# TD_0002-100_1.net
KiCad netlist of a schematic drawn in Altium Designer
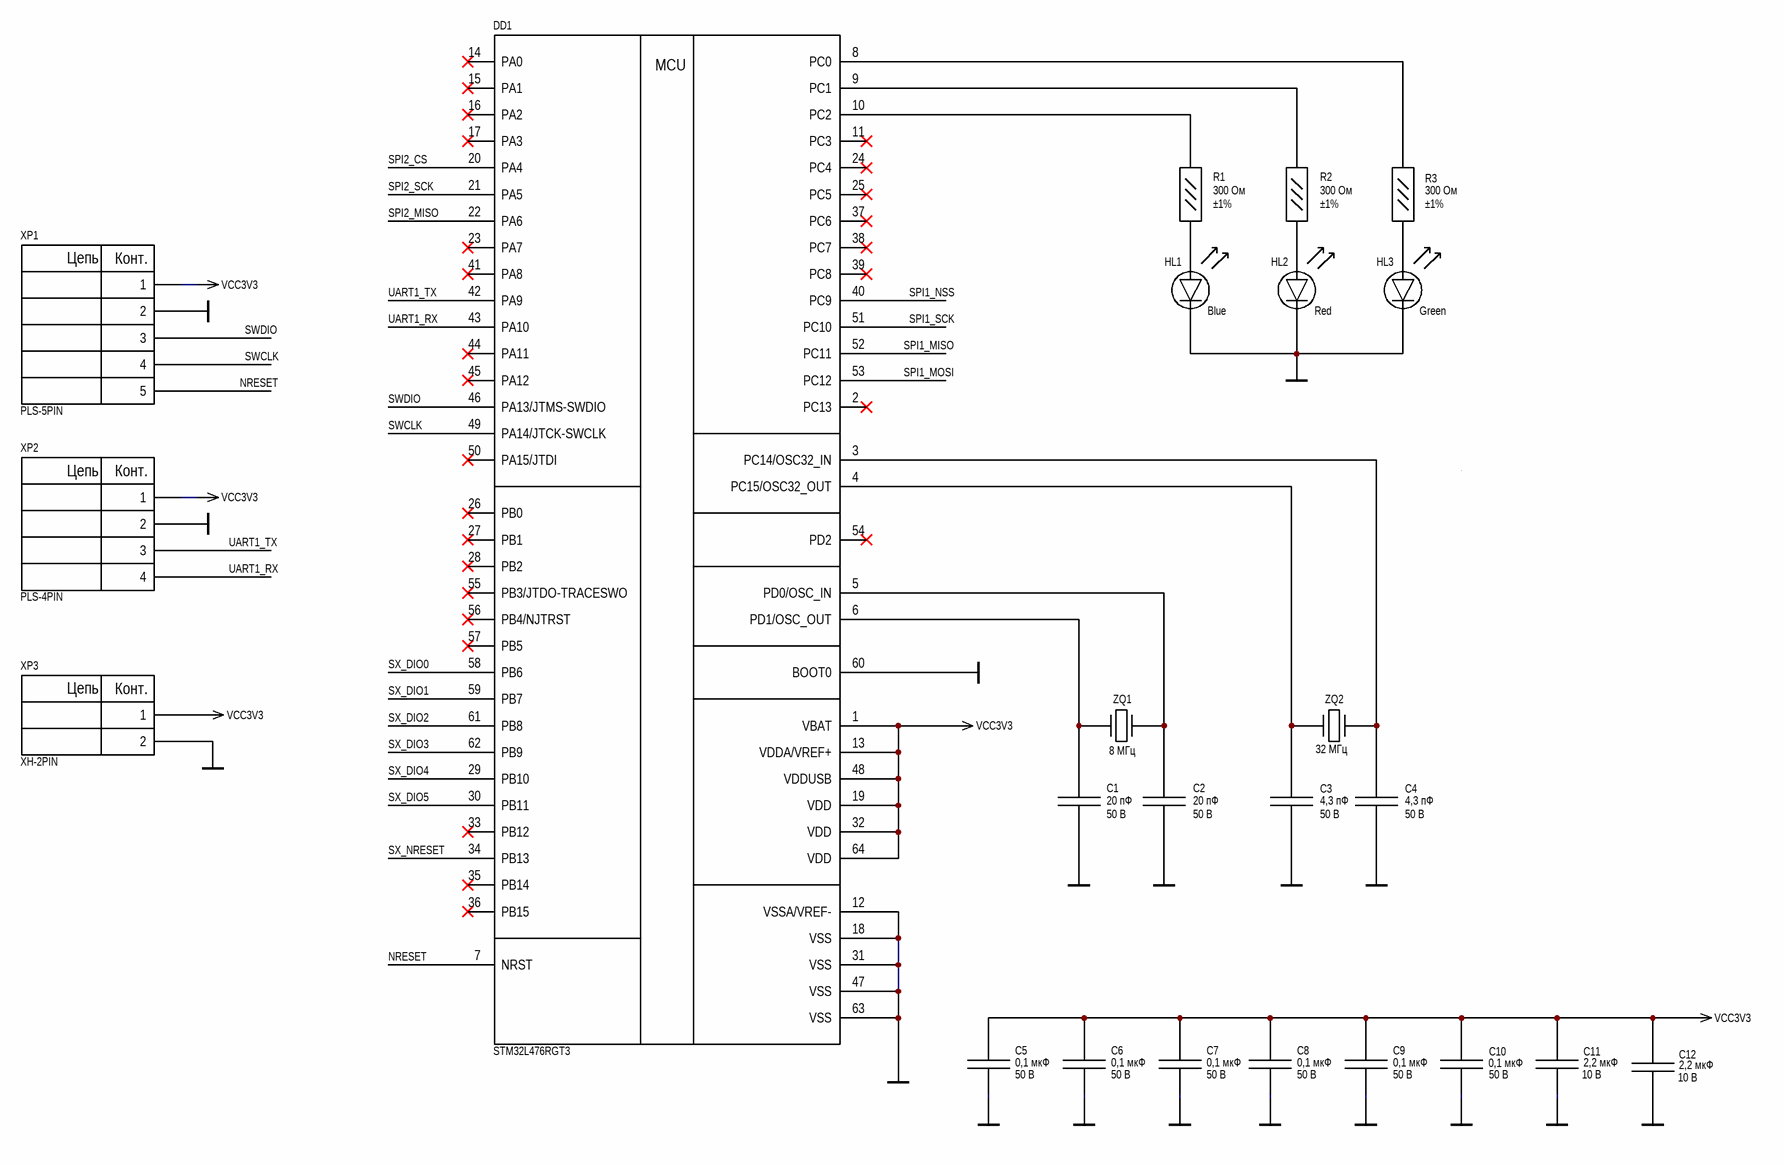
[diagram p0: TD.0002-100_1.SchDoc]

(export (version "E")
  (design (tool "Eeschema 10.0.6"))
  (components
    (comp (ref "C1")
      (value "20 пФ")
      (footprint "C_0402")
      (description "Chip Multilayer Ceramic Capacitor")
      (fields
        (field (name "PART NUMBER") "GCM1555C1H200JA16")
        (field (name "MANUFACTURER") "Murata")
        (field (name "VOLTAGE") "50 В")
      )
      (libsource (lib "Database_Libs") (part "Capacitor"))
    )
    (comp (ref "C2")
      (value "20 пФ")
      (footprint "C_0402")
      (description "Chip Multilayer Ceramic Capacitor")
      (fields
        (field (name "PART NUMBER") "GCM1555C1H200JA16")
        (field (name "MANUFACTURER") "Murata")
        (field (name "VOLTAGE") "50 В")
      )
      (libsource (lib "Database_Libs") (part "Capacitor"))
    )
    (comp (ref "C3")
      (value "4,3 пФ")
      (footprint "C_0402")
      (description "Chip Multilayer Ceramic Capacitor")
      (fields
        (field (name "PART NUMBER") "GCM1555C1H4R3BA16")
        (field (name "MANUFACTURER") "Murata")
        (field (name "VOLTAGE") "50 В")
      )
      (libsource (lib "Database_Libs") (part "Capacitor"))
    )
    (comp (ref "C4")
      (value "4,3 пФ")
      (footprint "C_0402")
      (description "Chip Multilayer Ceramic Capacitor")
      (fields
        (field (name "PART NUMBER") "GCM1555C1H4R3BA16")
        (field (name "MANUFACTURER") "Murata")
        (field (name "VOLTAGE") "50 В")
      )
      (libsource (lib "Database_Libs") (part "Capacitor"))
    )
    (comp (ref "C5")
      (value "0,1 мкФ")
      (footprint "C_0402")
      (description "Chip Multilayer Ceramic Capacitor")
      (fields
        (field (name "PART NUMBER") "GRM155R71H104KE14")
        (field (name "MANUFACTURER") "Murata")
        (field (name "VOLTAGE") "50 В")
      )
      (libsource (lib "Database_Libs") (part "Capacitor"))
    )
    (comp (ref "C6")
      (value "0,1 мкФ")
      (footprint "C_0402")
      (description "Chip Multilayer Ceramic Capacitor")
      (fields
        (field (name "PART NUMBER") "GRM155R71H104KE14")
        (field (name "MANUFACTURER") "Murata")
        (field (name "VOLTAGE") "50 В")
      )
      (libsource (lib "Database_Libs") (part "Capacitor"))
    )
    (comp (ref "C7")
      (value "0,1 мкФ")
      (footprint "C_0402")
      (description "Chip Multilayer Ceramic Capacitor")
      (fields
        (field (name "PART NUMBER") "GRM155R71H104KE14")
        (field (name "MANUFACTURER") "Murata")
        (field (name "VOLTAGE") "50 В")
      )
      (libsource (lib "Database_Libs") (part "Capacitor"))
    )
    (comp (ref "C8")
      (value "0,1 мкФ")
      (footprint "C_0402")
      (description "Chip Multilayer Ceramic Capacitor")
      (fields
        (field (name "PART NUMBER") "GRM155R71H104KE14")
        (field (name "MANUFACTURER") "Murata")
        (field (name "VOLTAGE") "50 В")
      )
      (libsource (lib "Database_Libs") (part "Capacitor"))
    )
    (comp (ref "C9")
      (value "0,1 мкФ")
      (footprint "C_0402")
      (description "Chip Multilayer Ceramic Capacitor")
      (fields
        (field (name "PART NUMBER") "GRM155R71H104KE14")
        (field (name "MANUFACTURER") "Murata")
        (field (name "VOLTAGE") "50 В")
      )
      (libsource (lib "Database_Libs") (part "Capacitor"))
    )
    (comp (ref "C10")
      (value "0,1 мкФ")
      (footprint "C_0402")
      (description "Chip Multilayer Ceramic Capacitor")
      (fields
        (field (name "PART NUMBER") "GRM155R71H104KE14")
        (field (name "MANUFACTURER") "Murata")
        (field (name "VOLTAGE") "50 В")
      )
      (libsource (lib "Database_Libs") (part "Capacitor"))
    )
    (comp (ref "C11")
      (value "2,2 мкФ")
      (footprint "C_0402")
      (description "Chip Multilayer Ceramic Capacitor")
      (fields
        (field (name "PART NUMBER") "GRM155C81A225ME44")
        (field (name "MANUFACTURER") "Murata")
        (field (name "VOLTAGE") "10 В")
      )
      (libsource (lib "Database_Libs") (part "Capacitor"))
    )
    (comp (ref "C12")
      (value "2,2 мкФ")
      (footprint "C_0402")
      (description "Chip Multilayer Ceramic Capacitor")
      (fields
        (field (name "PART NUMBER") "GRM155C81A225ME44")
        (field (name "MANUFACTURER") "Murata")
        (field (name "VOLTAGE") "10 В")
      )
      (libsource (lib "Database_Libs") (part "Capacitor"))
    )
    (comp (ref "DD1")
      (value "STM32L476RGT3")
      (footprint "FirstLib:LQFP_64")
      (fields (field (name "MANUFACTURER") "STMicroelectronics"))
      (libsource (lib "FirstLib") (part "STM32L476RGT3"))
    )
    (comp (ref "HL1")
      (value "TO-2013BC-BF")
      (footprint "LED_0805_BLUE")
      (description "Светодиод синий")
      (fields (field (name "COLOR") "Blue") (field (name "MANUFACTURER") "OASISTEK"))
      (libsource (lib "Database_Libs") (part "LED"))
    )
    (comp (ref "HL2")
      (value "TO-2013BC-MRE")
      (footprint "LED_0805_RED")
      (description "Светодиод красный")
      (fields (field (name "COLOR") "Red") (field (name "MANUFACTURER") "OASISTEK"))
      (libsource (lib "Database_Libs") (part "LED"))
    )
    (comp (ref "HL3")
      (value "TO-2013BC-PG")
      (footprint "LED_0805_GREEN")
      (description "Светодиод зеленый")
      (fields (field (name "COLOR") "Green") (field (name "MANUFACTURER") "OASISTEK"))
      (libsource (lib "Database_Libs") (part "LED"))
    )
    (comp (ref "R1")
      (value "300 Ом")
      (footprint "R_0402")
      (description "General Purpose")
      (fields
        (field (name "ACCURACY") "±1%")
        (field (name "PART NUMBER") "RC0100FR-07300RP")
        (field (name "VOLTAGE") "15 В")
      )
      (libsource (lib "Database_Libs") (part "Resistor_0.05W"))
    )
    (comp (ref "R2")
      (value "300 Ом")
      (footprint "R_0402")
      (description "General Purpose")
      (fields
        (field (name "ACCURACY") "±1%")
        (field (name "PART NUMBER") "RC0100FR-07300RP")
        (field (name "VOLTAGE") "15 В")
      )
      (libsource (lib "Database_Libs") (part "Resistor_0.05W"))
    )
    (comp (ref "R3")
      (value "300 Ом")
      (footprint "R_0402")
      (description "General Purpose")
      (fields
        (field (name "ACCURACY") "±1%")
        (field (name "PART NUMBER") "RC0100FR-07300RP")
        (field (name "VOLTAGE") "15 В")
      )
      (libsource (lib "Database_Libs") (part "Resistor_0.05W"))
    )
    (comp (ref "XP1")
      (value "PLS-5PIN")
      (footprint "FirstLib:PLS-5PIN")
      (libsource (lib "FirstLib") (part "PLS-5PIN"))
    )
    (comp (ref "XP2")
      (value "PLS-4PIN")
      (footprint "FirstLib:PLS-4PIN")
      (libsource (lib "FirstLib") (part "PLS-4PIN"))
    )
    (comp (ref "XP3")
      (value "XH-2PIN")
      (footprint "FirstLib:XH-2PIN")
      (fields (field (name "VOLTAGE") "250 V"))
      (libsource (lib "FirstLib") (part "XH-2PIN"))
    )
    (comp (ref "ZQ1")
      (value "8 МГц")
      (footprint "FirstLib:CM9V-T1A")
      (fields (field (name "Comment") "Quartz"))
      (libsource (lib "FirstLib") (part "Quartz"))
    )
    (comp (ref "ZQ2")
      (value "32 МГц")
      (footprint "FirstLib:CM9V-T1A")
      (fields (field (name "Comment") "Quartz"))
      (libsource (lib "FirstLib") (part "Quartz"))
    )
  )
  (nets
    (net (code "1") (name "/NRESET") (class "Default")
      (node (ref "DD1") (pin "7") (pinfunction "NRST_7") (pintype "passive"))
      (node (ref "XP1") (pin "5") (pinfunction "5_5") (pintype "passive"))
    )
    (net (code "2") (name "/SPI1_MISO") (class "Default")
      (node (ref "DD1") (pin "52") (pinfunction "PC11_52") (pintype "passive"))
    )
    (net (code "3") (name "/SPI1_MOSI") (class "Default")
      (node (ref "DD1") (pin "53") (pinfunction "PC12_53") (pintype "passive"))
    )
    (net (code "4") (name "/SPI1_NSS") (class "Default")
      (node (ref "DD1") (pin "40") (pinfunction "PC9_40") (pintype "passive"))
    )
    (net (code "5") (name "/SPI1_SCK") (class "Default")
      (node (ref "DD1") (pin "51") (pinfunction "PC10_51") (pintype "passive"))
    )
    (net (code "6") (name "/SPI2_CS") (class "Default")
      (node (ref "DD1") (pin "20") (pinfunction "PA4_20") (pintype "passive"))
    )
    (net (code "7") (name "/SPI2_MISO") (class "Default")
      (node (ref "DD1") (pin "22") (pinfunction "PA6_22") (pintype "passive"))
    )
    (net (code "8") (name "/SPI2_SCK") (class "Default")
      (node (ref "DD1") (pin "21") (pinfunction "PA5_21") (pintype "passive"))
    )
    (net (code "9") (name "/SWCLK") (class "Default")
      (node (ref "DD1") (pin "49") (pinfunction "PA14/JTCK-SWCLK_49") (pintype "passive"))
      (node (ref "XP1") (pin "4") (pinfunction "4_4") (pintype "passive"))
    )
    (net (code "10") (name "/SWDIO") (class "Default")
      (node (ref "DD1") (pin "46") (pinfunction "PA13/JTMS-SWDIO_46") (pintype "passive"))
      (node (ref "XP1") (pin "3") (pinfunction "3_3") (pintype "passive"))
    )
    (net (code "11") (name "/SX_DIO0") (class "Default")
      (node (ref "DD1") (pin "58") (pinfunction "PB6_58") (pintype "passive"))
    )
    (net (code "12") (name "/SX_DIO1") (class "Default")
      (node (ref "DD1") (pin "59") (pinfunction "PB7_59") (pintype "passive"))
    )
    (net (code "13") (name "/SX_DIO2") (class "Default")
      (node (ref "DD1") (pin "61") (pinfunction "PB8_61") (pintype "passive"))
    )
    (net (code "14") (name "/SX_DIO3") (class "Default")
      (node (ref "DD1") (pin "62") (pinfunction "PB9_62") (pintype "passive"))
    )
    (net (code "15") (name "/SX_DIO4") (class "Default")
      (node (ref "DD1") (pin "29") (pinfunction "PB10_29") (pintype "passive"))
    )
    (net (code "16") (name "/SX_DIO5") (class "Default")
      (node (ref "DD1") (pin "30") (pinfunction "PB11_30") (pintype "passive"))
    )
    (net (code "17") (name "/SX_NRESET") (class "Default")
      (node (ref "DD1") (pin "34") (pinfunction "PB13_34") (pintype "passive"))
    )
    (net (code "18") (name "/UART1_RX") (class "Default")
      (node (ref "DD1") (pin "43") (pinfunction "PA10_43") (pintype "passive"))
      (node (ref "XP2") (pin "4") (pinfunction "4_4") (pintype "passive"))
    )
    (net (code "19") (name "/UART1_TX") (class "Default")
      (node (ref "DD1") (pin "42") (pinfunction "PA9_42") (pintype "passive"))
      (node (ref "XP2") (pin "3") (pinfunction "3_3") (pintype "passive"))
    )
    (net (code "20") (name "GND") (class "Default")
      (node (ref "C1") (pin "2") (pinfunction "2_2") (pintype "passive"))
      (node (ref "C10") (pin "2") (pinfunction "2_2") (pintype "passive"))
      (node (ref "C11") (pin "2") (pinfunction "2_2") (pintype "passive"))
      (node (ref "C12") (pin "2") (pinfunction "2_2") (pintype "passive"))
      (node (ref "C2") (pin "2") (pinfunction "2_2") (pintype "passive"))
      (node (ref "C3") (pin "2") (pinfunction "2_2") (pintype "passive"))
      (node (ref "C4") (pin "2") (pinfunction "2_2") (pintype "passive"))
      (node (ref "C5") (pin "2") (pinfunction "2_2") (pintype "passive"))
      (node (ref "C6") (pin "2") (pinfunction "2_2") (pintype "passive"))
      (node (ref "C7") (pin "2") (pinfunction "2_2") (pintype "passive"))
      (node (ref "C8") (pin "2") (pinfunction "2_2") (pintype "passive"))
      (node (ref "C9") (pin "2") (pinfunction "2_2") (pintype "passive"))
      (node (ref "DD1") (pin "12") (pinfunction "VSSA/VREF-_12") (pintype "passive"))
      (node (ref "DD1") (pin "18") (pinfunction "VSS_18") (pintype "passive"))
      (node (ref "DD1") (pin "31") (pinfunction "VSS_31") (pintype "passive"))
      (node (ref "DD1") (pin "47") (pinfunction "VSS_47") (pintype "passive"))
      (node (ref "DD1") (pin "60") (pinfunction "BOOT0_60") (pintype "passive"))
      (node (ref "DD1") (pin "63") (pinfunction "VSS_63") (pintype "passive"))
      (node (ref "HL1") (pin "2") (pinfunction "2_2") (pintype "passive"))
      (node (ref "HL2") (pin "2") (pinfunction "2_2") (pintype "passive"))
      (node (ref "HL3") (pin "2") (pinfunction "2_2") (pintype "passive"))
      (node (ref "XP1") (pin "2") (pinfunction "2_2") (pintype "passive"))
      (node (ref "XP2") (pin "2") (pinfunction "2_2") (pintype "passive"))
      (node (ref "XP3") (pin "2") (pinfunction "2_2") (pintype "passive"))
    )
    (net (code "21") (name "Net-(DD1-PC0)") (class "Default")
      (node (ref "DD1") (pin "8") (pinfunction "PC0_8") (pintype "passive"))
      (node (ref "R3") (pin "2") (pinfunction "2_2") (pintype "passive"))
    )
    (net (code "22") (name "Net-(DD1-PC1)") (class "Default")
      (node (ref "DD1") (pin "9") (pinfunction "PC1_9") (pintype "passive"))
      (node (ref "R2") (pin "2") (pinfunction "2_2") (pintype "passive"))
    )
    (net (code "23") (name "Net-(DD1-PC2)") (class "Default")
      (node (ref "DD1") (pin "10") (pinfunction "PC2_10") (pintype "passive"))
      (node (ref "R1") (pin "2") (pinfunction "2_2") (pintype "passive"))
    )
    (net (code "24") (name "Net-(DD1-PC14{slash}OSC32_IN)") (class "Default")
      (node (ref "C4") (pin "1") (pinfunction "1_1") (pintype "passive"))
      (node (ref "DD1") (pin "3") (pinfunction "PC14/OSC32_IN_3") (pintype "passive"))
      (node (ref "ZQ2") (pin "2") (pinfunction "XO_2") (pintype "passive"))
    )
    (net (code "25") (name "Net-(DD1-PC15{slash}OSC32_OUT)") (class "Default")
      (node (ref "C3") (pin "1") (pinfunction "1_1") (pintype "passive"))
      (node (ref "DD1") (pin "4") (pinfunction "PC15/OSC32_OUT_4") (pintype "passive"))
      (node (ref "ZQ2") (pin "1") (pinfunction "XI_1") (pintype "passive"))
    )
    (net (code "26") (name "Net-(DD1-PD0{slash}OSC_IN)") (class "Default")
      (node (ref "C2") (pin "1") (pinfunction "1_1") (pintype "passive"))
      (node (ref "DD1") (pin "5") (pinfunction "PD0/OSC_IN_5") (pintype "passive"))
      (node (ref "ZQ1") (pin "1") (pinfunction "XI_1") (pintype "passive"))
    )
    (net (code "27") (name "Net-(DD1-PD1{slash}OSC_OUT)") (class "Default")
      (node (ref "C1") (pin "1") (pinfunction "1_1") (pintype "passive"))
      (node (ref "DD1") (pin "6") (pinfunction "PD1/OSC_OUT_6") (pintype "passive"))
      (node (ref "ZQ1") (pin "2") (pinfunction "XO_2") (pintype "passive"))
    )
    (net (code "28") (name "Net-(HL1-Pad1)") (class "Default")
      (node (ref "HL1") (pin "1") (pinfunction "1_1") (pintype "passive"))
      (node (ref "R1") (pin "1") (pinfunction "1_1") (pintype "passive"))
    )
    (net (code "29") (name "Net-(HL2-Pad1)") (class "Default")
      (node (ref "HL2") (pin "1") (pinfunction "1_1") (pintype "passive"))
      (node (ref "R2") (pin "1") (pinfunction "1_1") (pintype "passive"))
    )
    (net (code "30") (name "Net-(HL3-Pad1)") (class "Default")
      (node (ref "HL3") (pin "1") (pinfunction "1_1") (pintype "passive"))
      (node (ref "R3") (pin "1") (pinfunction "1_1") (pintype "passive"))
    )
    (net (code "31") (name "VCC3V3") (class "Default")
      (node (ref "C10") (pin "1") (pinfunction "1_1") (pintype "passive"))
      (node (ref "C11") (pin "1") (pinfunction "1_1") (pintype "passive"))
      (node (ref "C12") (pin "1") (pinfunction "1_1") (pintype "passive"))
      (node (ref "C5") (pin "1") (pinfunction "1_1") (pintype "passive"))
      (node (ref "C6") (pin "1") (pinfunction "1_1") (pintype "passive"))
      (node (ref "C7") (pin "1") (pinfunction "1_1") (pintype "passive"))
      (node (ref "C8") (pin "1") (pinfunction "1_1") (pintype "passive"))
      (node (ref "C9") (pin "1") (pinfunction "1_1") (pintype "passive"))
      (node (ref "DD1") (pin "1") (pinfunction "VBAT_1") (pintype "passive"))
      (node (ref "DD1") (pin "13") (pinfunction "VDDA/VREF+_13") (pintype "passive"))
      (node (ref "DD1") (pin "19") (pinfunction "VDD_19") (pintype "passive"))
      (node (ref "DD1") (pin "32") (pinfunction "VDD_32") (pintype "passive"))
      (node (ref "DD1") (pin "48") (pinfunction "VDDUSB_48") (pintype "passive"))
      (node (ref "DD1") (pin "64") (pinfunction "VDD_64") (pintype "passive"))
      (node (ref "XP1") (pin "1") (pinfunction "1_1") (pintype "passive"))
      (node (ref "XP2") (pin "1") (pinfunction "1_1") (pintype "passive"))
      (node (ref "XP3") (pin "1") (pinfunction "1_1") (pintype "passive"))
    )
    (net (code "32") (name "unconnected-(DD1-PA0-Pad14)") (class "Default")
      (node (ref "DD1") (pin "14") (pinfunction "PA0_14") (pintype "passive+no_connect"))
    )
    (net (code "33") (name "unconnected-(DD1-PA1-Pad15)") (class "Default")
      (node (ref "DD1") (pin "15") (pinfunction "PA1_15") (pintype "passive+no_connect"))
    )
    (net (code "34") (name "unconnected-(DD1-PA2-Pad16)") (class "Default")
      (node (ref "DD1") (pin "16") (pinfunction "PA2_16") (pintype "passive+no_connect"))
    )
    (net (code "35") (name "unconnected-(DD1-PA3-Pad17)") (class "Default")
      (node (ref "DD1") (pin "17") (pinfunction "PA3_17") (pintype "passive+no_connect"))
    )
    (net (code "36") (name "unconnected-(DD1-PA7-Pad23)") (class "Default")
      (node (ref "DD1") (pin "23") (pinfunction "PA7_23") (pintype "passive+no_connect"))
    )
    (net (code "37") (name "unconnected-(DD1-PA8-Pad41)") (class "Default")
      (node (ref "DD1") (pin "41") (pinfunction "PA8_41") (pintype "passive+no_connect"))
    )
    (net (code "38") (name "unconnected-(DD1-PA11-Pad44)") (class "Default")
      (node (ref "DD1") (pin "44") (pinfunction "PA11_44") (pintype "passive+no_connect"))
    )
    (net (code "39") (name "unconnected-(DD1-PA12-Pad45)") (class "Default")
      (node (ref "DD1") (pin "45") (pinfunction "PA12_45") (pintype "passive+no_connect"))
    )
    (net (code "40") (name "unconnected-(DD1-PA15{slash}JTDI-Pad50)") (class "Default")
      (node (ref "DD1") (pin "50") (pinfunction "PA15/JTDI_50") (pintype "passive+no_connect"))
    )
    (net (code "41") (name "unconnected-(DD1-PB0-Pad26)") (class "Default")
      (node (ref "DD1") (pin "26") (pinfunction "PB0_26") (pintype "passive+no_connect"))
    )
    (net (code "42") (name "unconnected-(DD1-PB1-Pad27)") (class "Default")
      (node (ref "DD1") (pin "27") (pinfunction "PB1_27") (pintype "passive+no_connect"))
    )
    (net (code "43") (name "unconnected-(DD1-PB2-Pad28)") (class "Default")
      (node (ref "DD1") (pin "28") (pinfunction "PB2_28") (pintype "passive+no_connect"))
    )
    (net (code "44") (name "unconnected-(DD1-PB3{slash}JTDO-TRACESWO-Pad55)") (class "Default")
      (node (ref "DD1") (pin "55") (pinfunction "PB3/JTDO-TRACESWO_55") (pintype "passive+no_connect"))
    )
    (net (code "45") (name "unconnected-(DD1-PB4{slash}NJTRST-Pad56)") (class "Default")
      (node (ref "DD1") (pin "56") (pinfunction "PB4/NJTRST_56") (pintype "passive+no_connect"))
    )
    (net (code "46") (name "unconnected-(DD1-PB5-Pad57)") (class "Default")
      (node (ref "DD1") (pin "57") (pinfunction "PB5_57") (pintype "passive+no_connect"))
    )
    (net (code "47") (name "unconnected-(DD1-PB12-Pad33)") (class "Default")
      (node (ref "DD1") (pin "33") (pinfunction "PB12_33") (pintype "passive+no_connect"))
    )
    (net (code "48") (name "unconnected-(DD1-PB14-Pad35)") (class "Default")
      (node (ref "DD1") (pin "35") (pinfunction "PB14_35") (pintype "passive+no_connect"))
    )
    (net (code "49") (name "unconnected-(DD1-PB15-Pad36)") (class "Default")
      (node (ref "DD1") (pin "36") (pinfunction "PB15_36") (pintype "passive+no_connect"))
    )
    (net (code "50") (name "unconnected-(DD1-PC3-Pad11)") (class "Default")
      (node (ref "DD1") (pin "11") (pinfunction "PC3_11") (pintype "passive+no_connect"))
    )
    (net (code "51") (name "unconnected-(DD1-PC4-Pad24)") (class "Default")
      (node (ref "DD1") (pin "24") (pinfunction "PC4_24") (pintype "passive+no_connect"))
    )
    (net (code "52") (name "unconnected-(DD1-PC5-Pad25)") (class "Default")
      (node (ref "DD1") (pin "25") (pinfunction "PC5_25") (pintype "passive+no_connect"))
    )
    (net (code "53") (name "unconnected-(DD1-PC6-Pad37)") (class "Default")
      (node (ref "DD1") (pin "37") (pinfunction "PC6_37") (pintype "passive+no_connect"))
    )
    (net (code "54") (name "unconnected-(DD1-PC7-Pad38)") (class "Default")
      (node (ref "DD1") (pin "38") (pinfunction "PC7_38") (pintype "passive+no_connect"))
    )
    (net (code "55") (name "unconnected-(DD1-PC8-Pad39)") (class "Default")
      (node (ref "DD1") (pin "39") (pinfunction "PC8_39") (pintype "passive+no_connect"))
    )
    (net (code "56") (name "unconnected-(DD1-PC13-Pad2)") (class "Default")
      (node (ref "DD1") (pin "2") (pinfunction "PC13_2") (pintype "passive+no_connect"))
    )
    (net (code "57") (name "unconnected-(DD1-PD2-Pad54)") (class "Default")
      (node (ref "DD1") (pin "54") (pinfunction "PD2_54") (pintype "passive+no_connect"))
    )
  )
)
